# Masa_Yard_mc_s.net
KiCad netlist of a schematic drawn in EAGLE
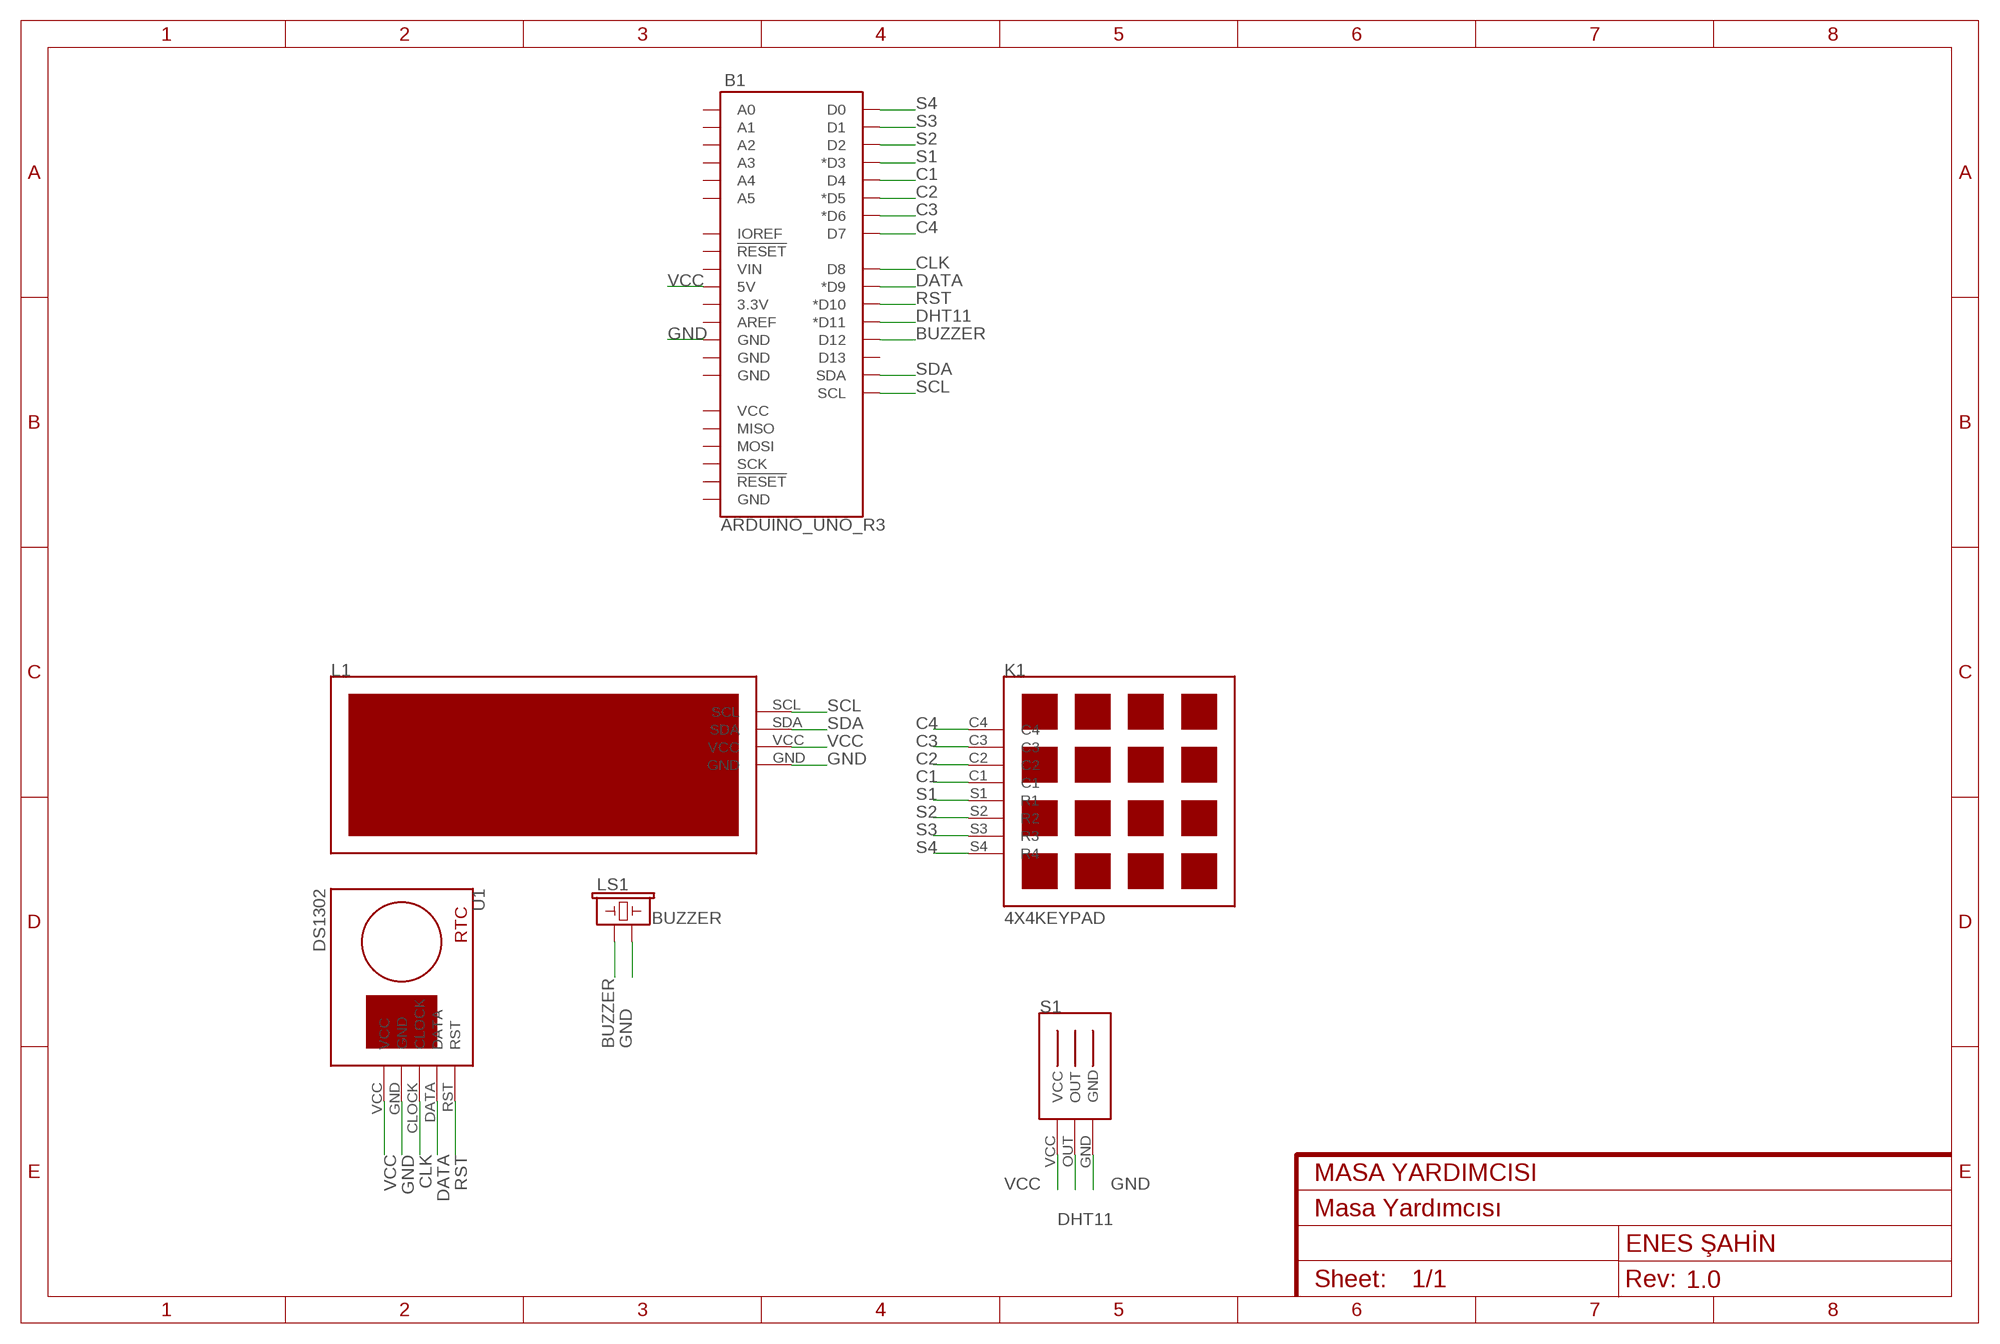
[diagram p0: schematic, sheet 1]

(export (version "E")
  (design (tool "Eeschema 10.0.6"))
  (components
    (comp (ref "B1")
      (value "ARDUINO_UNO_R3")
      (footprint "eagle-import:ARDUINO_R3")
      (libsource (lib "eagle-import") (part "ARDUINO_UNO_R3"))
    )
    (comp (ref "K1")
      (value "4X4KEYPAD")
      (footprint "eagle-import:4X4_KEYPAD")
      (libsource (lib "eagle-import") (part "4X4_KEYPAD"))
    )
    (comp (ref "L1")
      (value "16X2_LCD")
      (footprint "eagle-import:16X2_LCD")
      (libsource (lib "eagle-import") (part "16X2_LCD"))
    )
    (comp (ref "LS1")
      (value "BUZZER")
      (footprint "eagle-import:BUZZER-12MM")
      (libsource (lib "eagle-import") (part "BUZZER-PTH"))
    )
    (comp (ref "S1")
      (value "DHT11")
      (footprint "eagle-import:DHT11")
      (libsource (lib "eagle-import") (part "DHT11"))
    )
    (comp (ref "U1")
      (value "DS1302")
      (footprint "eagle-import:DS1302")
      (libsource (lib "eagle-import") (part "DS1302"))
    )
  )
  (nets
    (net (code "1") (name "/BUZZER") (class "Default")
      (node (ref "B1") (pin "D12") (pinfunction "D12_D12") (pintype "bidirectional"))
      (node (ref "LS1") (pin "+") (pinfunction "1_+") (pintype "passive"))
    )
    (net (code "2") (name "/C1") (class "Default")
      (node (ref "B1") (pin "D4") (pinfunction "D4_D4") (pintype "bidirectional"))
      (node (ref "K1") (pin "C1") (pinfunction "C1_C1") (pintype "bidirectional"))
    )
    (net (code "3") (name "/C2") (class "Default")
      (node (ref "B1") (pin "D5") (pinfunction "*D5_D5") (pintype "bidirectional"))
      (node (ref "K1") (pin "C2") (pinfunction "C2_C2") (pintype "bidirectional"))
    )
    (net (code "4") (name "/C3") (class "Default")
      (node (ref "B1") (pin "D6") (pinfunction "*D6_D6") (pintype "bidirectional"))
      (node (ref "K1") (pin "C3") (pinfunction "C3_C3") (pintype "bidirectional"))
    )
    (net (code "5") (name "/C4") (class "Default")
      (node (ref "B1") (pin "D7") (pinfunction "D7_D7") (pintype "bidirectional"))
      (node (ref "K1") (pin "C4") (pinfunction "C4_C4") (pintype "bidirectional"))
    )
    (net (code "6") (name "/CLK") (class "Default")
      (node (ref "B1") (pin "D8") (pinfunction "D8_D8") (pintype "bidirectional"))
      (node (ref "U1") (pin "CLOCK") (pinfunction "CLOCK_CLOCK") (pintype "bidirectional"))
    )
    (net (code "7") (name "/DATA") (class "Default")
      (node (ref "B1") (pin "D9") (pinfunction "*D9_D9") (pintype "bidirectional"))
      (node (ref "U1") (pin "DATA") (pinfunction "DATA_DATA") (pintype "bidirectional"))
    )
    (net (code "8") (name "/DHT11") (class "Default")
      (node (ref "B1") (pin "D11") (pinfunction "*D11_D11") (pintype "bidirectional"))
      (node (ref "S1") (pin "OUT") (pinfunction "OUT_OUT") (pintype "bidirectional"))
    )
    (net (code "9") (name "/GND") (class "Default")
      (node (ref "B1") (pin "GND@4") (pinfunction "GND_GND@4") (pintype "bidirectional"))
      (node (ref "L1") (pin "GND") (pinfunction "GND_GND") (pintype "bidirectional"))
      (node (ref "LS1") (pin "-") (pinfunction "2_-") (pintype "passive"))
      (node (ref "S1") (pin "GND") (pinfunction "GND_GND") (pintype "bidirectional"))
      (node (ref "U1") (pin "GND") (pinfunction "GND_GND") (pintype "bidirectional"))
    )
    (net (code "10") (name "/RST") (class "Default")
      (node (ref "B1") (pin "D10") (pinfunction "*D10_D10") (pintype "bidirectional"))
      (node (ref "U1") (pin "RST") (pinfunction "RST_RST") (pintype "bidirectional"))
    )
    (net (code "11") (name "/S1") (class "Default")
      (node (ref "B1") (pin "D3") (pinfunction "*D3_D3") (pintype "bidirectional"))
      (node (ref "K1") (pin "S1") (pinfunction "R1_S1") (pintype "bidirectional"))
    )
    (net (code "12") (name "/S2") (class "Default")
      (node (ref "B1") (pin "D2") (pinfunction "D2_D2") (pintype "bidirectional"))
      (node (ref "K1") (pin "S2") (pinfunction "R2_S2") (pintype "bidirectional"))
    )
    (net (code "13") (name "/S3") (class "Default")
      (node (ref "B1") (pin "D1") (pinfunction "D1_D1") (pintype "bidirectional"))
      (node (ref "K1") (pin "S3") (pinfunction "R3_S3") (pintype "bidirectional"))
    )
    (net (code "14") (name "/S4") (class "Default")
      (node (ref "B1") (pin "D0") (pinfunction "D0_D0") (pintype "bidirectional"))
      (node (ref "K1") (pin "S4") (pinfunction "R4_S4") (pintype "bidirectional"))
    )
    (net (code "15") (name "/SCL") (class "Default")
      (node (ref "B1") (pin "SCL") (pinfunction "SCL_SCL") (pintype "bidirectional"))
      (node (ref "L1") (pin "SCL") (pinfunction "SCL_SCL") (pintype "bidirectional"))
    )
    (net (code "16") (name "/SDA") (class "Default")
      (node (ref "B1") (pin "SDA") (pinfunction "SDA_SDA") (pintype "bidirectional"))
      (node (ref "L1") (pin "SDA") (pinfunction "SDA_SDA") (pintype "bidirectional"))
    )
    (net (code "17") (name "/VCC") (class "Default")
      (node (ref "B1") (pin "5V") (pinfunction "5V_5V") (pintype "bidirectional"))
      (node (ref "L1") (pin "VCC") (pinfunction "VCC_VCC") (pintype "bidirectional"))
      (node (ref "S1") (pin "VCC") (pinfunction "VCC_VCC") (pintype "bidirectional"))
      (node (ref "U1") (pin "VCC") (pinfunction "VCC_VCC") (pintype "bidirectional"))
    )
    (net (code "18") (name "unconnected-(B1-GND-PadGND@1)") (class "Default")
      (node (ref "B1") (pin "GND@1") (pinfunction "GND_GND@1") (pintype "bidirectional"))
    )
    (net (code "19") (name "unconnected-(B1-GND-PadGND@2)") (class "Default")
      (node (ref "B1") (pin "GND@2") (pinfunction "GND_GND@2") (pintype "bidirectional"))
    )
    (net (code "20") (name "unconnected-(B1-GND-PadGND@3)") (class "Default")
      (node (ref "B1") (pin "GND@3") (pinfunction "GND_GND@3") (pintype "bidirectional"))
    )
    (net (code "21") (name "unconnected-(B1-Pad3.3V)") (class "Default")
      (node (ref "B1") (pin "3.3V") (pinfunction "3.3V_3.3V") (pintype "bidirectional"))
    )
    (net (code "22") (name "unconnected-(B1-PadA0)") (class "Default")
      (node (ref "B1") (pin "A0") (pinfunction "A0_A0") (pintype "bidirectional"))
    )
    (net (code "23") (name "unconnected-(B1-PadA1)") (class "Default")
      (node (ref "B1") (pin "A1") (pinfunction "A1_A1") (pintype "bidirectional"))
    )
    (net (code "24") (name "unconnected-(B1-PadA2)") (class "Default")
      (node (ref "B1") (pin "A2") (pinfunction "A2_A2") (pintype "bidirectional"))
    )
    (net (code "25") (name "unconnected-(B1-PadA3)") (class "Default")
      (node (ref "B1") (pin "A3") (pinfunction "A3_A3") (pintype "bidirectional"))
    )
    (net (code "26") (name "unconnected-(B1-PadA4)") (class "Default")
      (node (ref "B1") (pin "A4") (pinfunction "A4_A4") (pintype "bidirectional"))
    )
    (net (code "27") (name "unconnected-(B1-PadA5)") (class "Default")
      (node (ref "B1") (pin "A5") (pinfunction "A5_A5") (pintype "bidirectional"))
    )
    (net (code "28") (name "unconnected-(B1-PadAREF)") (class "Default")
      (node (ref "B1") (pin "AREF") (pinfunction "AREF_AREF") (pintype "bidirectional"))
    )
    (net (code "29") (name "unconnected-(B1-PadD13)") (class "Default")
      (node (ref "B1") (pin "D13") (pinfunction "D13_D13") (pintype "bidirectional"))
    )
    (net (code "30") (name "unconnected-(B1-PadIOREF)") (class "Default")
      (node (ref "B1") (pin "IOREF") (pinfunction "IOREF_IOREF") (pintype "bidirectional"))
    )
    (net (code "31") (name "unconnected-(B1-PadMISO)") (class "Default")
      (node (ref "B1") (pin "MISO") (pinfunction "MISO_MISO") (pintype "bidirectional"))
    )
    (net (code "32") (name "unconnected-(B1-PadMOSI)") (class "Default")
      (node (ref "B1") (pin "MOSI") (pinfunction "MOSI_MOSI") (pintype "bidirectional"))
    )
    (net (code "33") (name "unconnected-(B1-PadSCK)") (class "Default")
      (node (ref "B1") (pin "SCK") (pinfunction "SCK_SCK") (pintype "bidirectional"))
    )
    (net (code "34") (name "unconnected-(B1-PadVCC)") (class "Default")
      (node (ref "B1") (pin "VCC") (pinfunction "VCC_VCC") (pintype "bidirectional"))
    )
    (net (code "35") (name "unconnected-(B1-PadVIN)") (class "Default")
      (node (ref "B1") (pin "VIN") (pinfunction "VIN_VIN") (pintype "bidirectional"))
    )
    (net (code "36") (name "unconnected-(B1-~{RESET}-PadRESET@1)") (class "Default")
      (node (ref "B1") (pin "RESET@1") (pinfunction "~{RESET}_RESET@1") (pintype "bidirectional"))
    )
    (net (code "37") (name "unconnected-(B1-~{RESET}-PadRESET@2)") (class "Default")
      (node (ref "B1") (pin "RESET@2") (pinfunction "~{RESET}_RESET@2") (pintype "bidirectional"))
    )
  )
)
